# biv2-batb_1a.net
KiCad netlist of a schematic drawn in Altium Designer
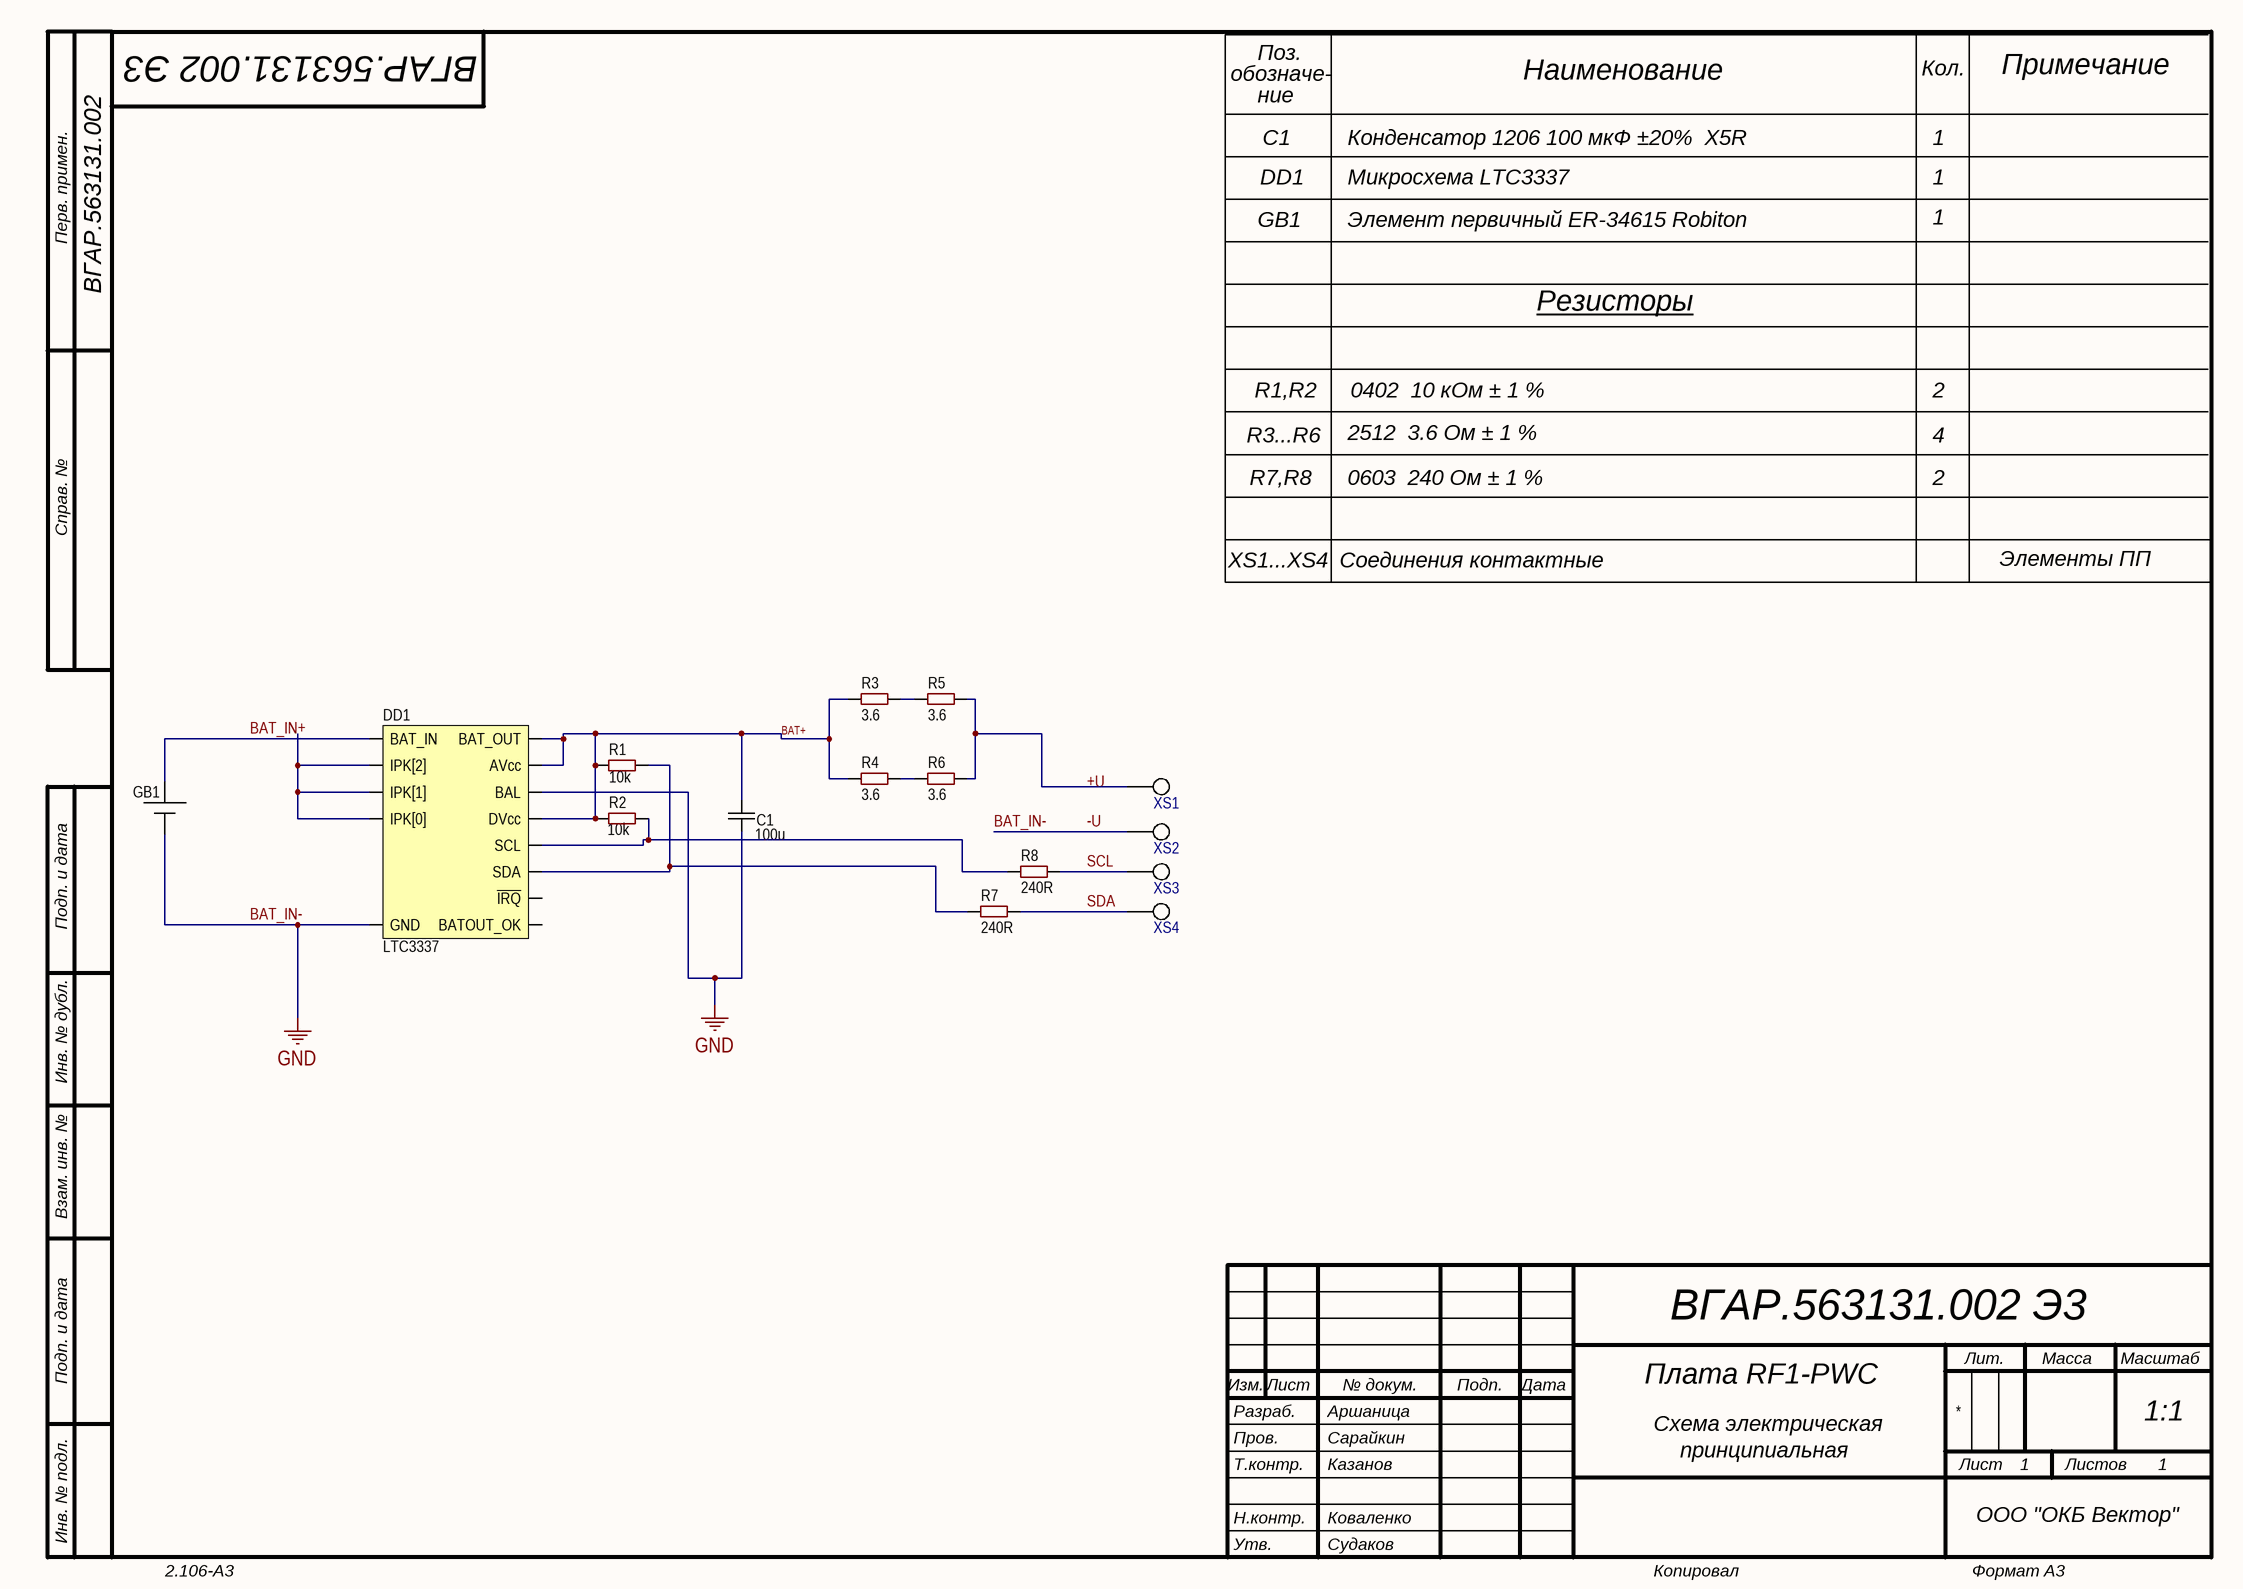
[diagram p0: biv2-batb_1a.SchDoc]

(export (version "E")
  (design (tool "Eeschema 10.0.6"))
  (components
    (comp (ref "C1")
      (value "100u")
      (footprint "CAP: 1206")
      (fields
        (field (name "MANUFACTURER") "Yageo")
        (field (name "PARTNUMBER") "CC1206KRX7R9BB104")
        (field (name "VALUEMANUFACTURERPARTNUMBER") "Ceramic capacitor, 100u, X7R, ±10%, 6V, 1206, -55...+125°C")
      )
      (libsource (lib "capacitor") (part "Ceramic_1206"))
    )
    (comp (ref "DD1")
      (value "LTC3337")
      (footprint "12-LFCSP")
      (description "Battery SOH monitor")
      (libsource (lib "ic-sensor") (part "LTC3337"))
    )
    (comp (ref "R1")
      (value "10k")
      (footprint "RES: 0402")
      (fields
        (field (name "MANUFACTURER") "Yageo")
        (field (name "PARTNUMBER") "RC0402JR-07100RL")
        (field (name "VALUEMANUFACTURERPARTNUMBER") "Resistor film, 10k, , 0402, 0.063W, -55...+125°C")
      )
      (libsource (lib "resistor") (part "Resistor_0402"))
    )
    (comp (ref "R2")
      (value "10k")
      (footprint "RES: 0402")
      (fields
        (field (name "MANUFACTURER") "Yageo")
        (field (name "PARTNUMBER") "RC0402JR-07100RL")
        (field (name "VALUEMANUFACTURERPARTNUMBER") "Resistor film, 10k, , 0402, 0.063W, -55...+125°C")
      )
      (libsource (lib "resistor") (part "Resistor_0402"))
    )
    (comp (ref "R3")
      (value "3.6")
      (footprint "RES: 2512")
      (fields
        (field (name "MANUFACTURER") "Yageo")
        (field (name "PARTNUMBER") "RC2512JK-07100RL")
        (field (name "VALUEMANUFACTURERPARTNUMBER") "Resistor film, 3.6, ±5%, 2512, 1W, -55...+125°C")
      )
      (libsource (lib "resistor") (part "Resistor_2512"))
    )
    (comp (ref "R4")
      (value "3.6")
      (footprint "RES: 2512")
      (fields
        (field (name "MANUFACTURER") "Yageo")
        (field (name "PARTNUMBER") "RC2512JK-07100RL")
        (field (name "VALUEMANUFACTURERPARTNUMBER") "Resistor film, 3.6, ±5%, 2512, 1W, -55...+125°C")
      )
      (libsource (lib "resistor") (part "Resistor_2512"))
    )
    (comp (ref "R5")
      (value "3.6")
      (footprint "RES: 2512")
      (fields
        (field (name "MANUFACTURER") "Yageo")
        (field (name "PARTNUMBER") "RC2512JK-07100RL")
        (field (name "VALUEMANUFACTURERPARTNUMBER") "Resistor film, 3.6, ±5%, 2512, 1W, -55...+125°C")
      )
      (libsource (lib "resistor") (part "Resistor_2512"))
    )
    (comp (ref "R6")
      (value "3.6")
      (footprint "RES: 2512")
      (fields
        (field (name "MANUFACTURER") "Yageo")
        (field (name "PARTNUMBER") "RC2512JK-07100RL")
        (field (name "VALUEMANUFACTURERPARTNUMBER") "Resistor film, 3.6, ±5%, 2512, 1W, -55...+125°C")
      )
      (libsource (lib "resistor") (part "Resistor_2512"))
    )
    (comp (ref "R7")
      (value "240R")
      (footprint "RES: 0603")
      (fields
        (field (name "MANUFACTURER") "Yageo")
        (field (name "PARTNUMBER") "RC0603JR-07100RL")
        (field (name "VALUEMANUFACTURERPARTNUMBER") "Resistor film, 240R, ±5%, 0603, 0.1W, -55...+125°C")
      )
      (libsource (lib "resistor") (part "Resistor_0603"))
    )
    (comp (ref "R8")
      (value "240R")
      (footprint "RES: 0603")
      (fields
        (field (name "MANUFACTURER") "Yageo")
        (field (name "PARTNUMBER") "RC0603JR-07100RL")
        (field (name "VALUEMANUFACTURERPARTNUMBER") "Resistor film, 240R, ±5%, 0603, 0.1W, -55...+125°C")
      )
      (libsource (lib "resistor") (part "Resistor_0603"))
    )
    (comp (ref "XS1")
      (value "Testpoint_HS1mm")
      (footprint "TestPoint(without 3D)")
      (libsource (lib "connector") (part "Testpoint_HS1mm"))
    )
    (comp (ref "XS2")
      (value "Testpoint_HS1mm")
      (footprint "TestPoint(without 3D)")
      (libsource (lib "connector") (part "Testpoint_HS1mm"))
    )
    (comp (ref "XS3")
      (value "Testpoint_HS1mm")
      (footprint "TestPoint(without 3D)")
      (libsource (lib "connector") (part "Testpoint_HS1mm"))
    )
    (comp (ref "XS4")
      (value "Testpoint_HS1mm")
      (footprint "TestPoint(without 3D)")
      (libsource (lib "connector") (part "Testpoint_HS1mm"))
    )
  )
  (nets
    (net (code "2") (name "/BAT+") (class "Default")
      (node (ref "C1") (pin "2") (pinfunction "2_2") (pintype "passive"))
      (node (ref "DD1") (pin "12") (pinfunction "BAT_OUT_12") (pintype "passive"))
      (node (ref "DD1") (pin "2") (pinfunction "AVcc_2") (pintype "power_in"))
      (node (ref "DD1") (pin "3") (pinfunction "DVcc_3") (pintype "power_in"))
      (node (ref "R1") (pin "1") (pinfunction "1_1") (pintype "passive"))
      (node (ref "R2") (pin "1") (pinfunction "1_1") (pintype "passive"))
      (node (ref "R3") (pin "1") (pinfunction "1_1") (pintype "passive"))
      (node (ref "R4") (pin "1") (pinfunction "1_1") (pintype "passive"))
    )
    (net (code "3") (name "/BAT_IN+") (class "Default")
      (node (ref "DD1") (pin "11") (pinfunction "BAT_IN_11") (pintype "passive"))
    )
    (net (code "4") (name "/SCL") (class "Default")
      (node (ref "R8") (pin "2") (pinfunction "2_2") (pintype "passive"))
      (node (ref "XS3") (pin "1") (pinfunction "1_1") (pintype "passive"))
    )
    (net (code "5") (name "/SDA") (class "Default")
      (node (ref "R7") (pin "2") (pinfunction "2_2") (pintype "passive"))
      (node (ref "XS4") (pin "1") (pinfunction "1_1") (pintype "passive"))
    )
    (net (code "6") (name "GND") (class "Default")
      (node (ref "C1") (pin "1") (pinfunction "1_1") (pintype "passive"))
      (node (ref "DD1") (pin "1") (pinfunction "BAL_1") (pintype "power_in"))
      (node (ref "DD1") (pin "13") (pinfunction "GND_13") (pintype "power_in"))
      (node (ref "XS2") (pin "1") (pinfunction "1_1") (pintype "passive"))
    )
    (net (code "7") (name "Net-(DD1-IPK[0])") (class "Default")
      (node (ref "DD1") (pin "10") (pinfunction "IPK[0]_10") (pintype "passive"))
      (node (ref "DD1") (pin "8") (pinfunction "IPK[2]_8") (pintype "passive"))
      (node (ref "DD1") (pin "9") (pinfunction "IPK[1]_9") (pintype "passive"))
    )
    (net (code "8") (name "Net-(DD1-SCL)") (class "Default")
      (node (ref "DD1") (pin "4") (pinfunction "SCL_4") (pintype "power_in"))
      (node (ref "R2") (pin "2") (pinfunction "2_2") (pintype "passive"))
      (node (ref "R8") (pin "1") (pinfunction "1_1") (pintype "passive"))
    )
    (net (code "9") (name "Net-(DD1-SDA)") (class "Default")
      (node (ref "DD1") (pin "5") (pinfunction "SDA_5") (pintype "power_in"))
      (node (ref "R1") (pin "2") (pinfunction "2_2") (pintype "passive"))
      (node (ref "R7") (pin "1") (pinfunction "1_1") (pintype "passive"))
    )
    (net (code "10") (name "Net-(R3-Pad2)") (class "Default")
      (node (ref "R3") (pin "2") (pinfunction "2_2") (pintype "passive"))
      (node (ref "R5") (pin "1") (pinfunction "1_1") (pintype "passive"))
    )
    (net (code "11") (name "Net-(R4-Pad2)") (class "Default")
      (node (ref "R4") (pin "2") (pinfunction "2_2") (pintype "passive"))
      (node (ref "R6") (pin "1") (pinfunction "1_1") (pintype "passive"))
    )
    (net (code "12") (name "Net-(R5-Pad2)") (class "Default")
      (node (ref "R5") (pin "2") (pinfunction "2_2") (pintype "passive"))
      (node (ref "R6") (pin "2") (pinfunction "2_2") (pintype "passive"))
      (node (ref "XS1") (pin "1") (pinfunction "1_1") (pintype "passive"))
    )
    (net (code "13") (name "unconnected-(DD1-BATOUT_OK-Pad7)") (class "Default")
      (node (ref "DD1") (pin "7") (pinfunction "BATOUT_OK_7") (pintype "power_in"))
    )
    (net (code "14") (name "unconnected-(DD1-~{IRQ}-Pad6)") (class "Default")
      (node (ref "DD1") (pin "6") (pinfunction "~{IRQ}_6") (pintype "power_in"))
    )
  )
)
